# peripherial_schematic.net
KiCad netlist of a schematic drawn in EAGLE
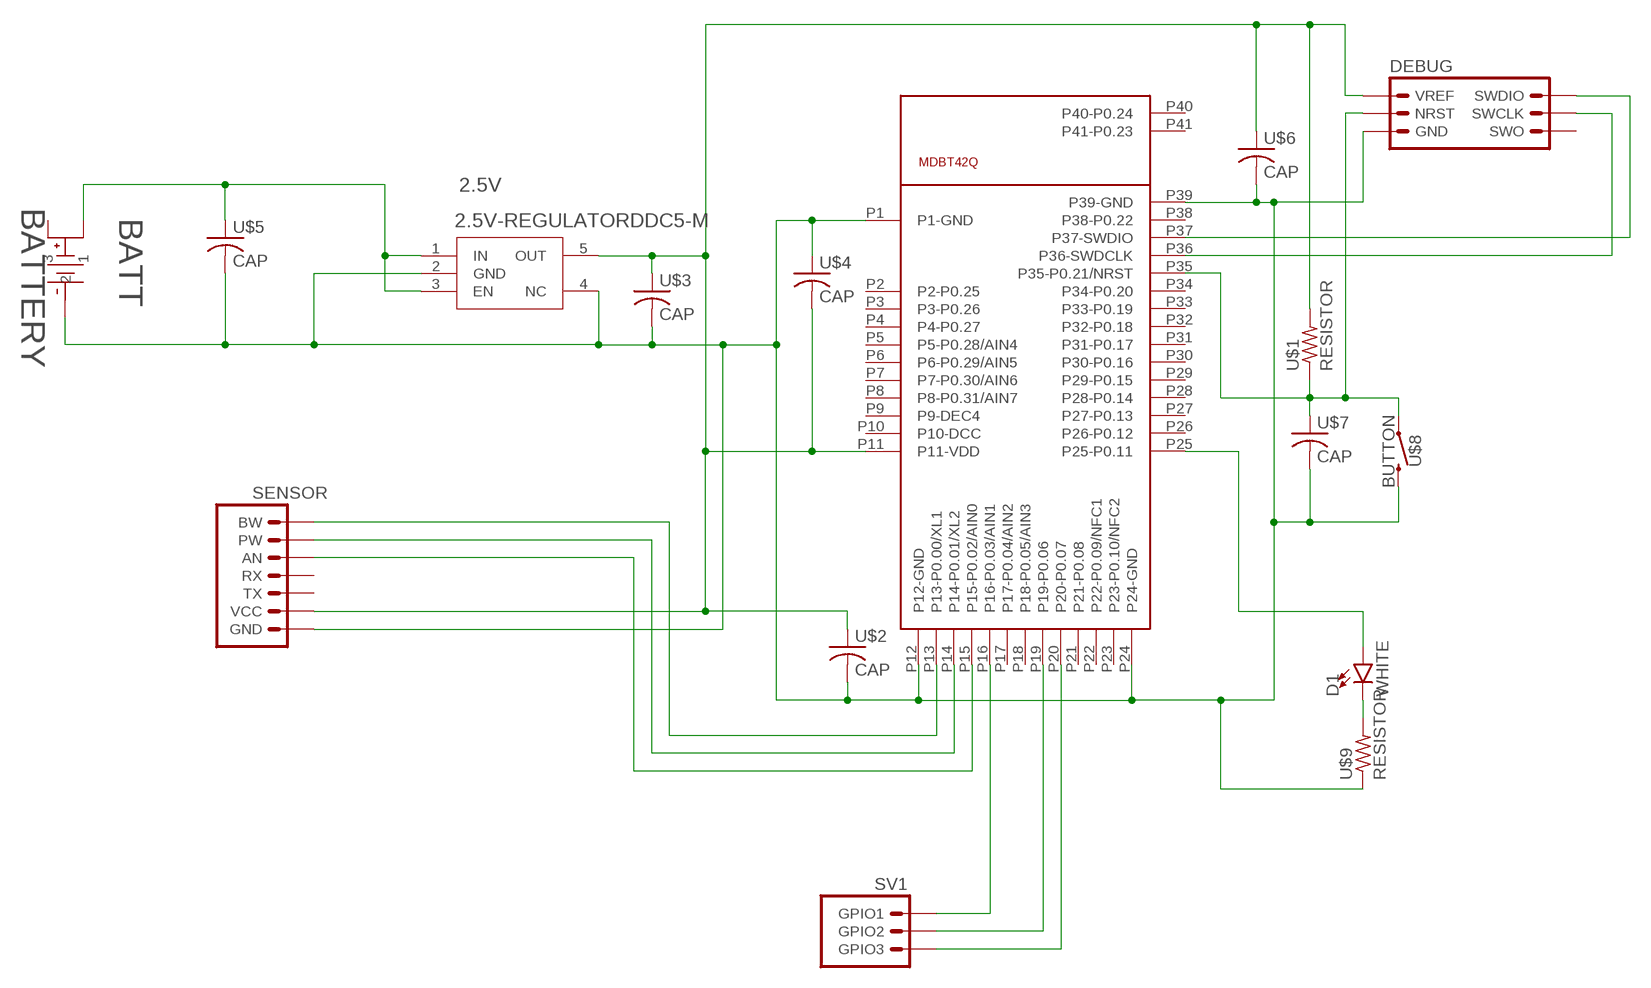
[diagram p0: schematic, sheet 1]

(export (version "E")
  (design (tool "Eeschema 10.0.6"))
  (components
    (comp (ref "2.5V")
      (value "2.5V-REGULATORDDC5-M")
      (footprint "eagle-import:DDC5-M")
      (fields (field (name "MANUFACTURER_PART_NUMBER") "TLV70025DDCR"))
      (libsource (lib "eagle-import") (part "2.5V-REGULATORDDC5-M"))
    )
    (comp (ref "BATT")
      (value "BATTERY")
      (footprint "eagle-import:BAT_HLDR_2468")
      (fields (field (name "MANUFACTURER_PART_NUMBER") "2468"))
      (libsource (lib "eagle-import") (part "BATTERY"))
    )
    (comp (ref "D1")
      (value "WHITE")
      (footprint "eagle-import:LED-1206")
      (libsource (lib "eagle-import") (part "LED_12061206"))
    )
    (comp (ref "DEBUG")
      (value "DEBUGGER")
      (footprint "eagle-import:MA03-2")
      (libsource (lib "eagle-import") (part "DEBUGGER"))
    )
    (comp (ref "MICRO")
      (value "MDBT42Q")
      (footprint "eagle-import:MDBT40")
      (libsource (lib "eagle-import") (part "MDBT42Q"))
    )
    (comp (ref "SENSOR")
      (value "SENSORHEADER")
      (footprint "eagle-import:MA07-1")
      (libsource (lib "eagle-import") (part "SENSORHEADER"))
    )
    (comp (ref "SV1")
      (value "GPIO")
      (footprint "eagle-import:MA03-1")
      (libsource (lib "eagle-import") (part "GPIO"))
    )
    (comp (ref "U$1")
      (value "RESISTOR")
      (footprint "eagle-import:M1206")
      (libsource (lib "eagle-import") (part "RESISTOR"))
    )
    (comp (ref "U$2")
      (value "CAP")
      (footprint "eagle-import:C1206")
      (libsource (lib "eagle-import") (part "CAP"))
    )
    (comp (ref "U$3")
      (value "CAP")
      (footprint "eagle-import:C1206")
      (libsource (lib "eagle-import") (part "CAP"))
    )
    (comp (ref "U$4")
      (value "CAP")
      (footprint "eagle-import:C1206")
      (libsource (lib "eagle-import") (part "CAP"))
    )
    (comp (ref "U$5")
      (value "CAP")
      (footprint "eagle-import:C1206")
      (libsource (lib "eagle-import") (part "CAP"))
    )
    (comp (ref "U$6")
      (value "CAP")
      (footprint "eagle-import:C1206")
      (libsource (lib "eagle-import") (part "CAP"))
    )
    (comp (ref "U$7")
      (value "CAP")
      (footprint "eagle-import:C1206")
      (libsource (lib "eagle-import") (part "CAP"))
    )
    (comp (ref "U$8")
      (value "BUTTON")
      (footprint "eagle-import:TACTILE_SWITCH_SMD_6.2MM_TALL")
      (libsource (lib "eagle-import") (part "BUTTON"))
    )
    (comp (ref "U$9")
      (value "RESISTOR")
      (footprint "eagle-import:M1206")
      (libsource (lib "eagle-import") (part "RESISTOR"))
    )
  )
  (nets
    (net (code "1") (name "Net-(2.5V-EN)") (class "Default")
      (node (ref "2.5V") (pin "1") (pinfunction "IN_1") (pintype "input"))
      (node (ref "2.5V") (pin "3") (pinfunction "EN_3") (pintype "passive"))
      (node (ref "BATT") (pin "1") (pinfunction "1_1") (pintype "passive"))
      (node (ref "U$5") (pin "1") (pinfunction "1_1") (pintype "passive"))
    )
    (net (code "2") (name "Net-(2.5V-GND)") (class "Default")
      (node (ref "2.5V") (pin "2") (pinfunction "GND_2") (pintype "power_in"))
      (node (ref "2.5V") (pin "4") (pinfunction "NC_4") (pintype "passive"))
      (node (ref "BATT") (pin "2") (pinfunction "2_2") (pintype "passive"))
      (node (ref "DEBUG") (pin "2") (pinfunction "GND_2") (pintype "passive"))
      (node (ref "MICRO") (pin "P1") (pinfunction "P1-GND_P1") (pintype "bidirectional"))
      (node (ref "MICRO") (pin "P12") (pinfunction "P12-GND_P12") (pintype "bidirectional"))
      (node (ref "MICRO") (pin "P24") (pinfunction "P24-GND_P24") (pintype "bidirectional"))
      (node (ref "MICRO") (pin "P39") (pinfunction "P39-GND_P39") (pintype "bidirectional"))
      (node (ref "SENSOR") (pin "1") (pinfunction "GND_1") (pintype "passive"))
      (node (ref "U$2") (pin "2") (pinfunction "2_2") (pintype "passive"))
      (node (ref "U$3") (pin "2") (pinfunction "2_2") (pintype "passive"))
      (node (ref "U$4") (pin "1") (pinfunction "1_1") (pintype "passive"))
      (node (ref "U$5") (pin "2") (pinfunction "2_2") (pintype "passive"))
      (node (ref "U$6") (pin "2") (pinfunction "2_2") (pintype "passive"))
      (node (ref "U$7") (pin "2") (pinfunction "2_2") (pintype "passive"))
      (node (ref "U$8") (pin "TOP1") (pinfunction "2_TOP1") (pintype "passive"))
      (node (ref "U$8") (pin "TOP2") (pinfunction "2_TOP2") (pintype "passive"))
      (node (ref "U$9") (pin "1") (pinfunction "1_1") (pintype "passive"))
    )
    (net (code "3") (name "Net-(2.5V-OUT)") (class "Default")
      (node (ref "2.5V") (pin "5") (pinfunction "OUT_5") (pintype "output"))
      (node (ref "DEBUG") (pin "6") (pinfunction "VREF_6") (pintype "passive"))
      (node (ref "MICRO") (pin "P11") (pinfunction "P11-VDD_P11") (pintype "bidirectional"))
      (node (ref "SENSOR") (pin "2") (pinfunction "VCC_2") (pintype "passive"))
      (node (ref "U$1") (pin "2") (pinfunction "2_2") (pintype "passive"))
      (node (ref "U$2") (pin "1") (pinfunction "1_1") (pintype "passive"))
      (node (ref "U$3") (pin "1") (pinfunction "1_1") (pintype "passive"))
      (node (ref "U$4") (pin "2") (pinfunction "2_2") (pintype "passive"))
      (node (ref "U$6") (pin "1") (pinfunction "1_1") (pintype "passive"))
    )
    (net (code "4") (name "Net-(D1-PadC)") (class "Default")
      (node (ref "D1") (pin "C") (pinfunction "C_C") (pintype "passive"))
      (node (ref "U$9") (pin "2") (pinfunction "2_2") (pintype "passive"))
    )
    (net (code "5") (name "Net-(DEBUG-NRST)") (class "Default")
      (node (ref "DEBUG") (pin "4") (pinfunction "NRST_4") (pintype "passive"))
      (node (ref "MICRO") (pin "P35") (pinfunction "P35-P0.21/NRST_P35") (pintype "bidirectional"))
      (node (ref "U$1") (pin "1") (pinfunction "1_1") (pintype "passive"))
      (node (ref "U$7") (pin "1") (pinfunction "1_1") (pintype "passive"))
      (node (ref "U$8") (pin "BOTTOM1") (pinfunction "1_BOTTOM1") (pintype "passive"))
      (node (ref "U$8") (pin "BOTTOM2") (pinfunction "1_BOTTOM2") (pintype "passive"))
    )
    (net (code "6") (name "Net-(DEBUG-SWCLK)") (class "Default")
      (node (ref "DEBUG") (pin "3") (pinfunction "SWCLK_3") (pintype "passive"))
      (node (ref "MICRO") (pin "P36") (pinfunction "P36-SWDCLK_P36") (pintype "bidirectional"))
    )
    (net (code "7") (name "Net-(DEBUG-SWDIO)") (class "Default")
      (node (ref "DEBUG") (pin "5") (pinfunction "SWDIO_5") (pintype "passive"))
      (node (ref "MICRO") (pin "P37") (pinfunction "P37-SWDIO_P37") (pintype "bidirectional"))
    )
    (net (code "8") (name "Net-(MICRO-P13-P0.00{slash}XL1)") (class "Default")
      (node (ref "MICRO") (pin "P13") (pinfunction "P13-P0.00/XL1_P13") (pintype "bidirectional"))
      (node (ref "SENSOR") (pin "7") (pinfunction "BW_7") (pintype "passive"))
    )
    (net (code "9") (name "Net-(MICRO-P14-P0.01{slash}XL2)") (class "Default")
      (node (ref "MICRO") (pin "P14") (pinfunction "P14-P0.01/XL2_P14") (pintype "bidirectional"))
      (node (ref "SENSOR") (pin "6") (pinfunction "PW_6") (pintype "passive"))
    )
    (net (code "10") (name "Net-(MICRO-P15-P0.02{slash}AIN0)") (class "Default")
      (node (ref "MICRO") (pin "P15") (pinfunction "P15-P0.02/AIN0_P15") (pintype "bidirectional"))
      (node (ref "SENSOR") (pin "5") (pinfunction "AN_5") (pintype "passive"))
    )
    (net (code "11") (name "Net-(MICRO-P16-P0.03{slash}AIN1)") (class "Default")
      (node (ref "MICRO") (pin "P16") (pinfunction "P16-P0.03/AIN1_P16") (pintype "bidirectional"))
      (node (ref "SV1") (pin "3") (pinfunction "GPIO1_3") (pintype "passive"))
    )
    (net (code "12") (name "Net-(MICRO-P19-P0.06)") (class "Default")
      (node (ref "MICRO") (pin "P19") (pinfunction "P19-P0.06_P19") (pintype "bidirectional"))
      (node (ref "SV1") (pin "2") (pinfunction "GPIO2_2") (pintype "passive"))
    )
    (net (code "13") (name "Net-(MICRO-P20-P0.07)") (class "Default")
      (node (ref "MICRO") (pin "P20") (pinfunction "P20-P0.07_P20") (pintype "bidirectional"))
      (node (ref "SV1") (pin "1") (pinfunction "GPIO3_1") (pintype "passive"))
    )
    (net (code "14") (name "Net-(MICRO-P25-P0.11)") (class "Default")
      (node (ref "D1") (pin "A") (pinfunction "A_A") (pintype "passive"))
      (node (ref "MICRO") (pin "P25") (pinfunction "P25-P0.11_P25") (pintype "bidirectional"))
    )
    (net (code "15") (name "unconnected-(BATT-Pad3)") (class "Default")
      (node (ref "BATT") (pin "3") (pinfunction "3_3") (pintype "passive"))
    )
    (net (code "16") (name "unconnected-(DEBUG-SWO-Pad1)") (class "Default")
      (node (ref "DEBUG") (pin "1") (pinfunction "SWO_1") (pintype "passive"))
    )
    (net (code "17") (name "unconnected-(MICRO-P2-P0.25-PadP2)") (class "Default")
      (node (ref "MICRO") (pin "P2") (pinfunction "P2-P0.25_P2") (pintype "bidirectional"))
    )
    (net (code "18") (name "unconnected-(MICRO-P3-P0.26-PadP3)") (class "Default")
      (node (ref "MICRO") (pin "P3") (pinfunction "P3-P0.26_P3") (pintype "bidirectional"))
    )
    (net (code "19") (name "unconnected-(MICRO-P4-P0.27-PadP4)") (class "Default")
      (node (ref "MICRO") (pin "P4") (pinfunction "P4-P0.27_P4") (pintype "bidirectional"))
    )
    (net (code "20") (name "unconnected-(MICRO-P5-P0.28{slash}AIN4-PadP5)") (class "Default")
      (node (ref "MICRO") (pin "P5") (pinfunction "P5-P0.28/AIN4_P5") (pintype "bidirectional"))
    )
    (net (code "21") (name "unconnected-(MICRO-P6-P0.29{slash}AIN5-PadP6)") (class "Default")
      (node (ref "MICRO") (pin "P6") (pinfunction "P6-P0.29/AIN5_P6") (pintype "bidirectional"))
    )
    (net (code "22") (name "unconnected-(MICRO-P7-P0.30{slash}AIN6-PadP7)") (class "Default")
      (node (ref "MICRO") (pin "P7") (pinfunction "P7-P0.30/AIN6_P7") (pintype "bidirectional"))
    )
    (net (code "23") (name "unconnected-(MICRO-P8-P0.31{slash}AIN7-PadP8)") (class "Default")
      (node (ref "MICRO") (pin "P8") (pinfunction "P8-P0.31/AIN7_P8") (pintype "bidirectional"))
    )
    (net (code "24") (name "unconnected-(MICRO-P9-DEC4-PadP9)") (class "Default")
      (node (ref "MICRO") (pin "P9") (pinfunction "P9-DEC4_P9") (pintype "bidirectional"))
    )
    (net (code "25") (name "unconnected-(MICRO-P10-DCC-PadP10)") (class "Default")
      (node (ref "MICRO") (pin "P10") (pinfunction "P10-DCC_P10") (pintype "bidirectional"))
    )
    (net (code "26") (name "unconnected-(MICRO-P17-P0.04{slash}AIN2-PadP17)") (class "Default")
      (node (ref "MICRO") (pin "P17") (pinfunction "P17-P0.04/AIN2_P17") (pintype "bidirectional"))
    )
    (net (code "27") (name "unconnected-(MICRO-P18-P0.05{slash}AIN3-PadP18)") (class "Default")
      (node (ref "MICRO") (pin "P18") (pinfunction "P18-P0.05/AIN3_P18") (pintype "bidirectional"))
    )
    (net (code "28") (name "unconnected-(MICRO-P21-P0.08-PadP21)") (class "Default")
      (node (ref "MICRO") (pin "P21") (pinfunction "P21-P0.08_P21") (pintype "bidirectional"))
    )
    (net (code "29") (name "unconnected-(MICRO-P22-P0.09{slash}NFC1-PadP22)") (class "Default")
      (node (ref "MICRO") (pin "P22") (pinfunction "P22-P0.09/NFC1_P22") (pintype "bidirectional"))
    )
    (net (code "30") (name "unconnected-(MICRO-P23-P0.10{slash}NFC2-PadP23)") (class "Default")
      (node (ref "MICRO") (pin "P23") (pinfunction "P23-P0.10/NFC2_P23") (pintype "bidirectional"))
    )
    (net (code "31") (name "unconnected-(MICRO-P26-P0.12-PadP26)") (class "Default")
      (node (ref "MICRO") (pin "P26") (pinfunction "P26-P0.12_P26") (pintype "bidirectional"))
    )
    (net (code "32") (name "unconnected-(MICRO-P27-P0.13-PadP27)") (class "Default")
      (node (ref "MICRO") (pin "P27") (pinfunction "P27-P0.13_P27") (pintype "bidirectional"))
    )
    (net (code "33") (name "unconnected-(MICRO-P28-P0.14-PadP28)") (class "Default")
      (node (ref "MICRO") (pin "P28") (pinfunction "P28-P0.14_P28") (pintype "bidirectional"))
    )
    (net (code "34") (name "unconnected-(MICRO-P29-P0.15-PadP29)") (class "Default")
      (node (ref "MICRO") (pin "P29") (pinfunction "P29-P0.15_P29") (pintype "bidirectional"))
    )
    (net (code "35") (name "unconnected-(MICRO-P30-P0.16-PadP30)") (class "Default")
      (node (ref "MICRO") (pin "P30") (pinfunction "P30-P0.16_P30") (pintype "bidirectional"))
    )
    (net (code "36") (name "unconnected-(MICRO-P31-P0.17-PadP31)") (class "Default")
      (node (ref "MICRO") (pin "P31") (pinfunction "P31-P0.17_P31") (pintype "bidirectional"))
    )
    (net (code "37") (name "unconnected-(MICRO-P32-P0.18-PadP32)") (class "Default")
      (node (ref "MICRO") (pin "P32") (pinfunction "P32-P0.18_P32") (pintype "bidirectional"))
    )
    (net (code "38") (name "unconnected-(MICRO-P33-P0.19-PadP33)") (class "Default")
      (node (ref "MICRO") (pin "P33") (pinfunction "P33-P0.19_P33") (pintype "bidirectional"))
    )
    (net (code "39") (name "unconnected-(MICRO-P34-P0.20-PadP34)") (class "Default")
      (node (ref "MICRO") (pin "P34") (pinfunction "P34-P0.20_P34") (pintype "bidirectional"))
    )
    (net (code "40") (name "unconnected-(MICRO-P38-P0.22-PadP38)") (class "Default")
      (node (ref "MICRO") (pin "P38") (pinfunction "P38-P0.22_P38") (pintype "bidirectional"))
    )
    (net (code "41") (name "unconnected-(MICRO-P40-P0.24-PadP40)") (class "Default")
      (node (ref "MICRO") (pin "P40") (pinfunction "P40-P0.24_P40") (pintype "bidirectional"))
    )
    (net (code "42") (name "unconnected-(MICRO-P41-P0.23-PadP41)") (class "Default")
      (node (ref "MICRO") (pin "P41") (pinfunction "P41-P0.23_P41") (pintype "bidirectional"))
    )
    (net (code "43") (name "unconnected-(SENSOR-RX-Pad4)") (class "Default")
      (node (ref "SENSOR") (pin "4") (pinfunction "RX_4") (pintype "passive"))
    )
    (net (code "44") (name "unconnected-(SENSOR-TX-Pad3)") (class "Default")
      (node (ref "SENSOR") (pin "3") (pinfunction "TX_3") (pintype "passive"))
    )
  )
)
